# 2-EXS82.net
KiCad netlist of a schematic drawn in Altium Designer
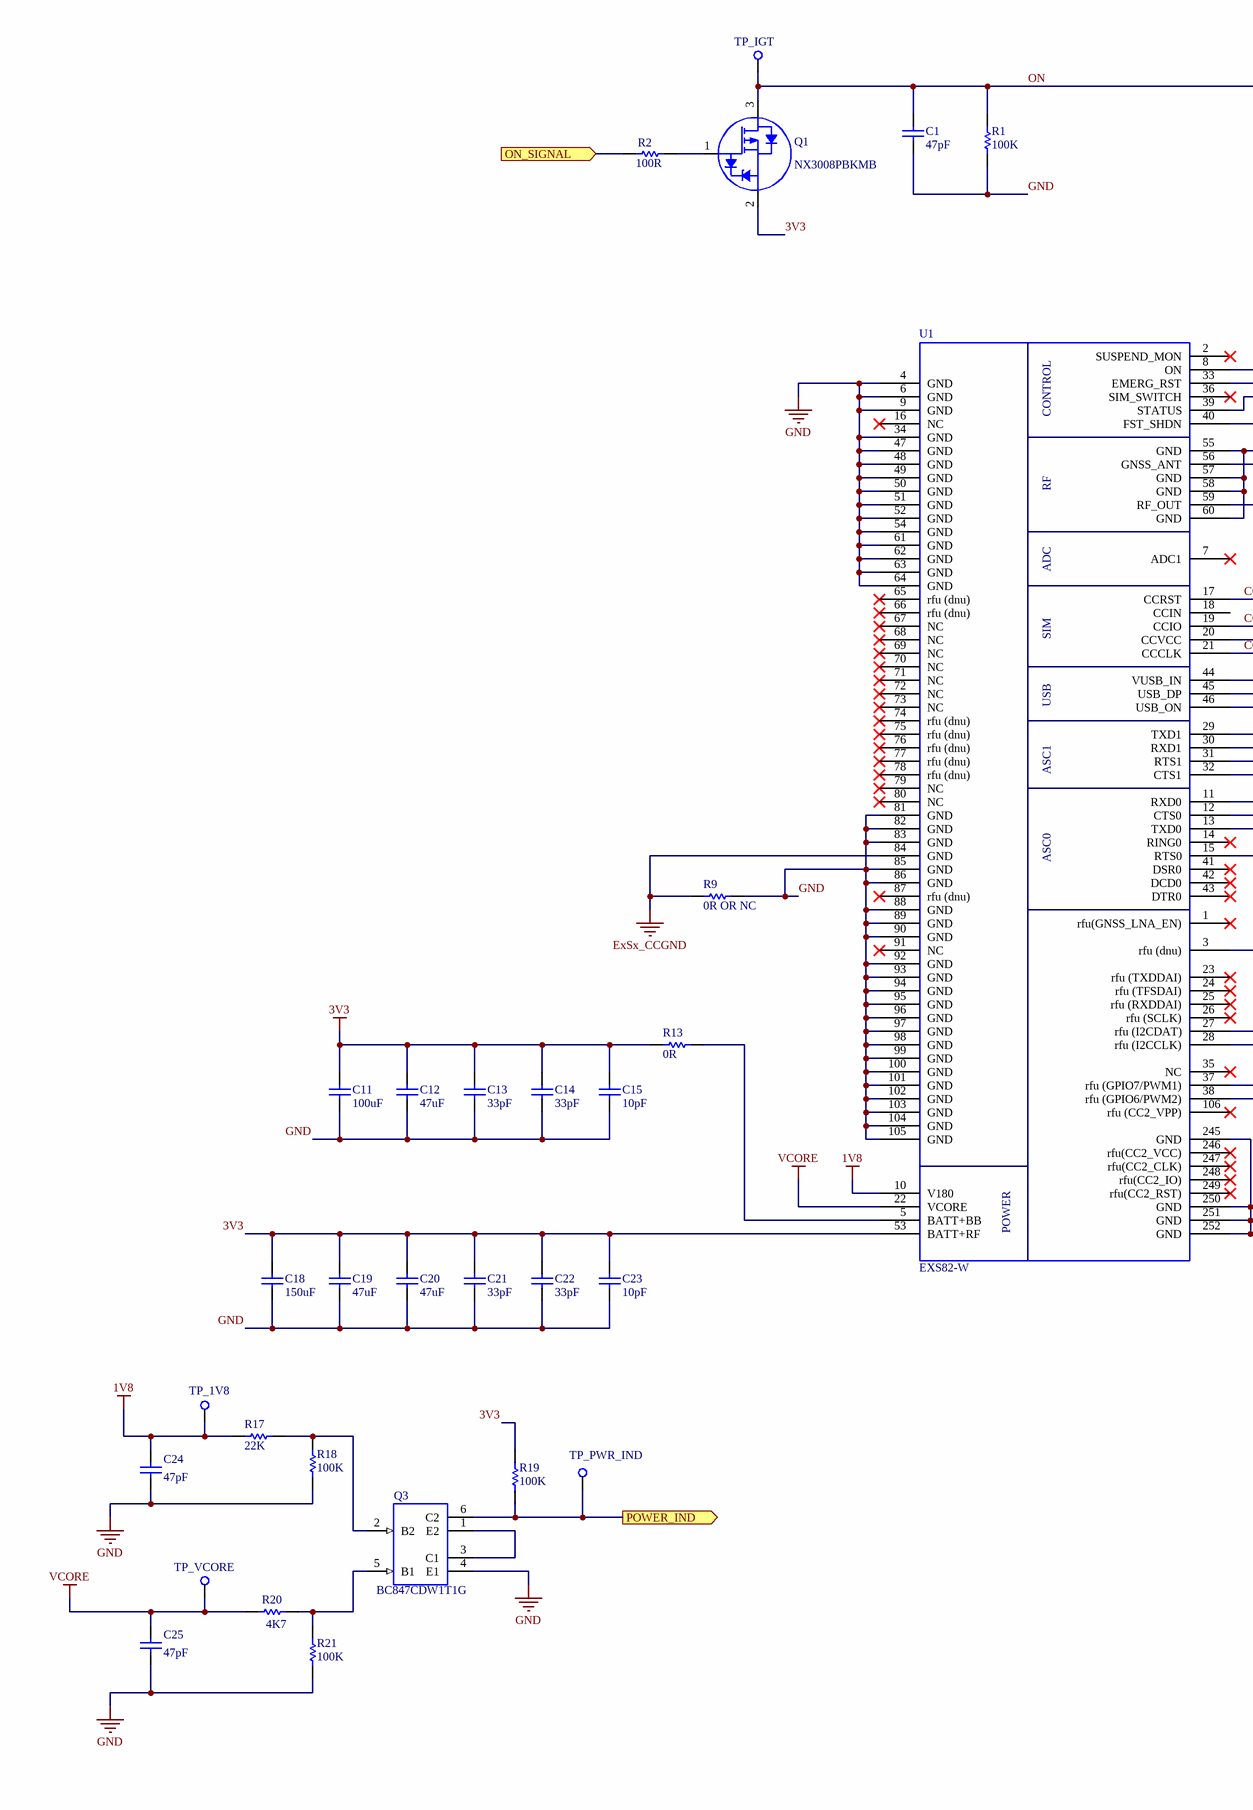
[diagram p0: 2-EXS82.SchDoc, left]
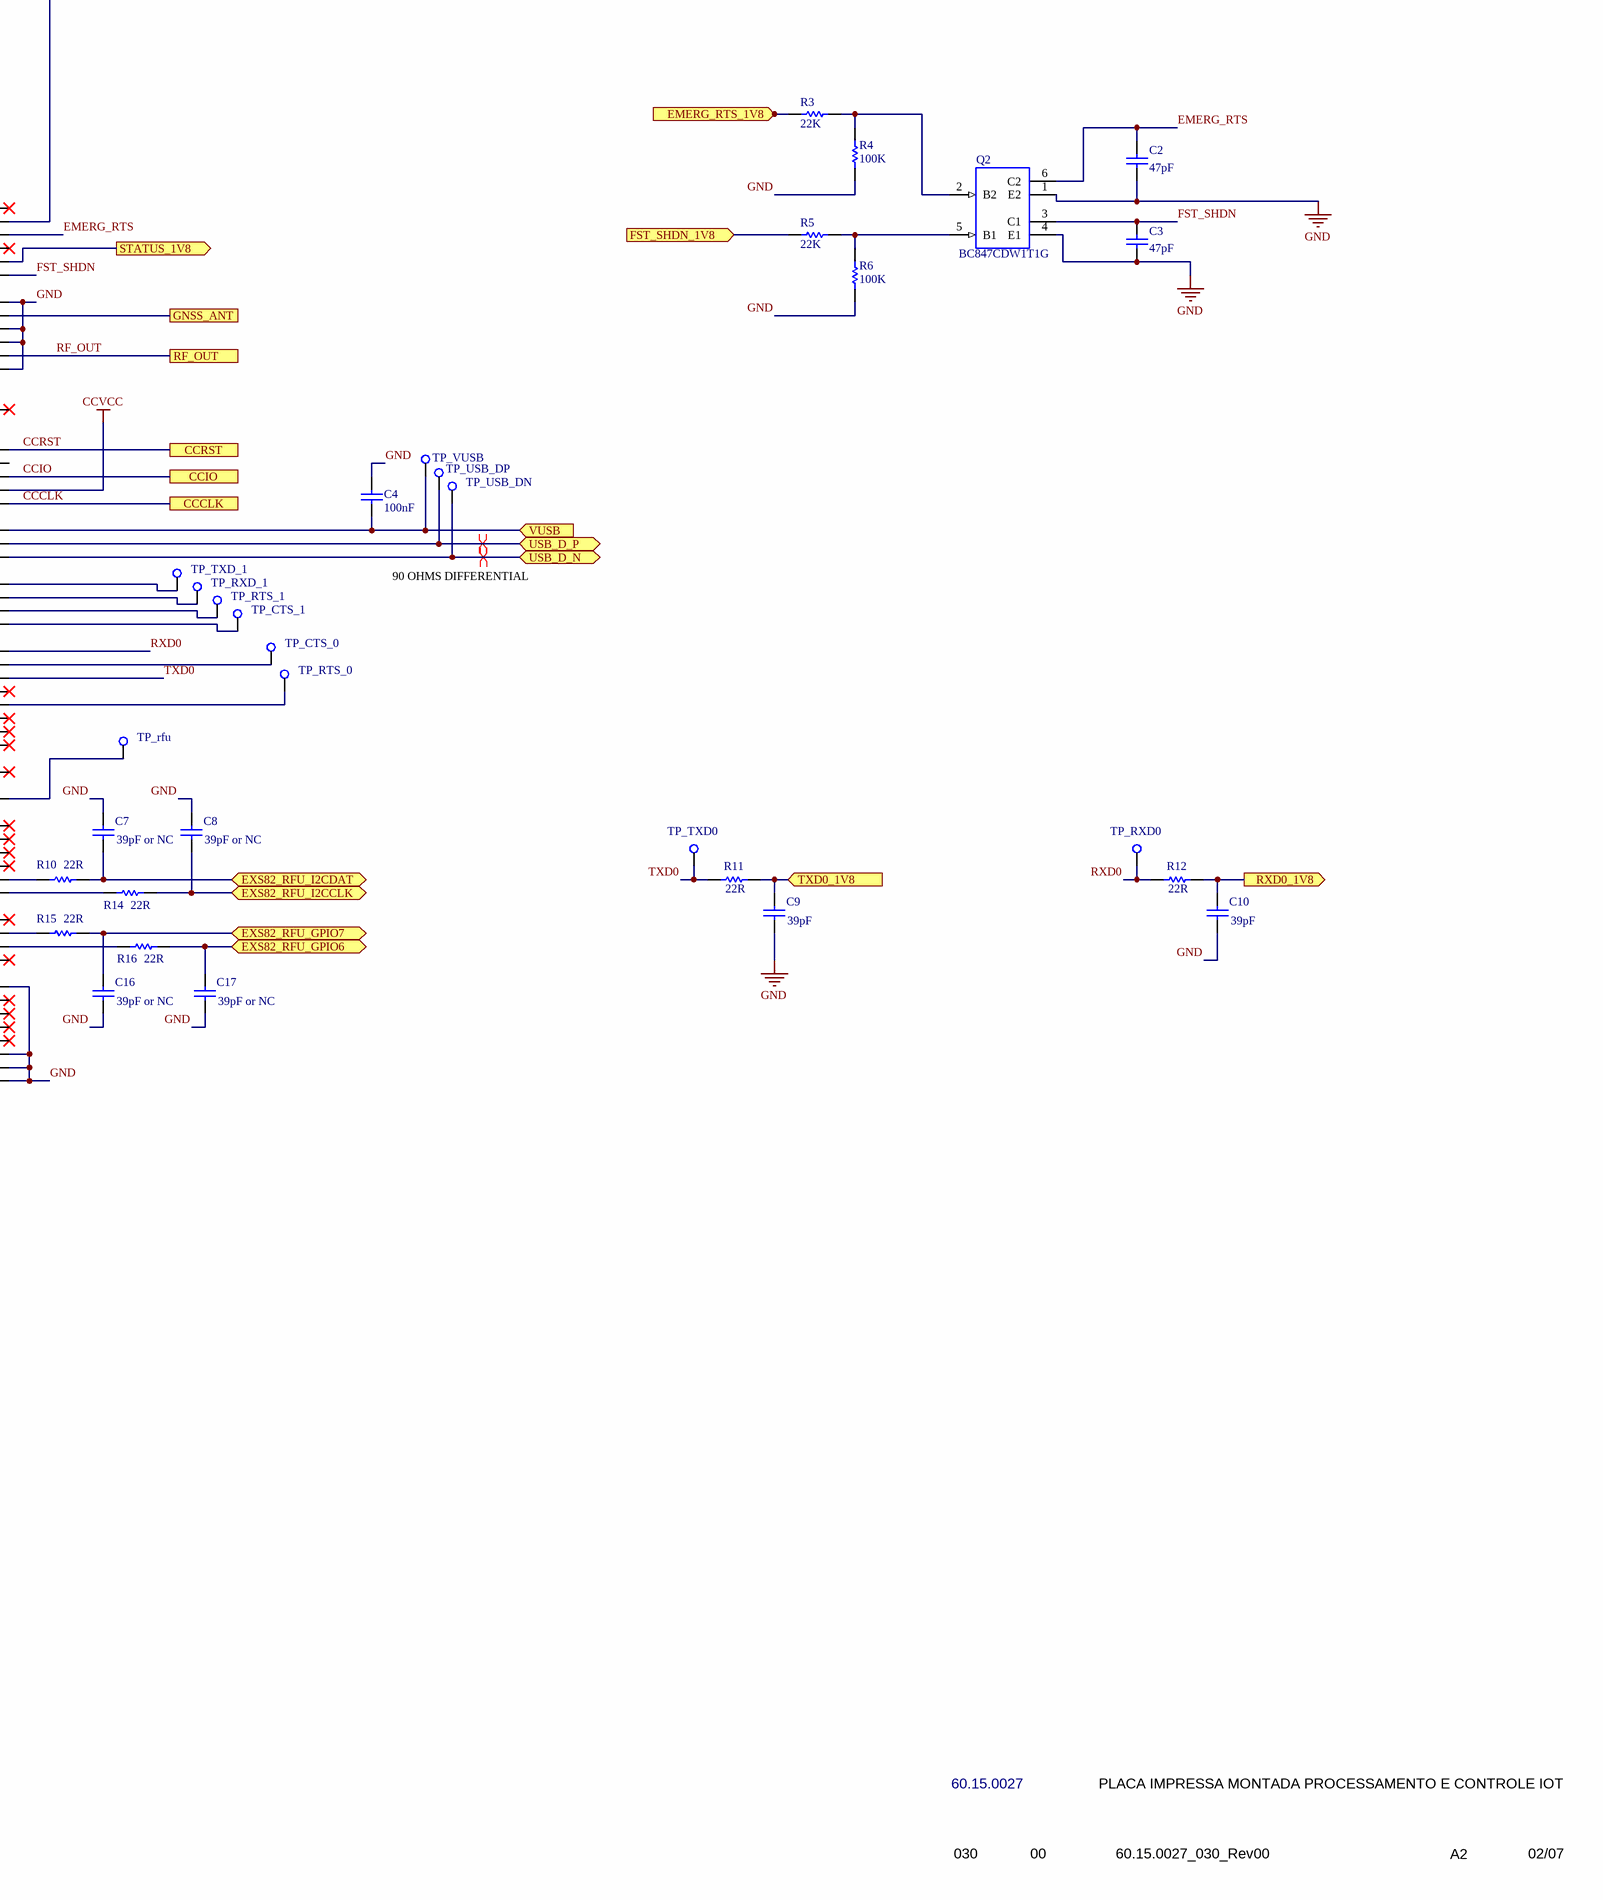
[diagram p1: 2-EXS82.SchDoc, right]

(export (version "E")
  (design (tool "Eeschema 10.0.6"))
  (components
    (comp (ref "C1")
      (value "16.23.0798")
      (footprint "16.23.0798")
      (description "CAPACITOR CERAMICO 47pF 10V 5% C0G SMD 0201")
      (fields (field (name "ALTIUM_UNNAMED_1") "47pF"))
      (libsource (lib "OMNI-CAPACITORES") (part "16.23.0798"))
    )
    (comp (ref "C2")
      (value "16.23.0798")
      (footprint "16.23.0798")
      (description "CAPACITOR CERAMICO 47pF 10V 5% C0G SMD 0201")
      (fields (field (name "ALTIUM_UNNAMED_1") "47pF"))
      (libsource (lib "OMNI-CAPACITORES") (part "16.23.0798"))
    )
    (comp (ref "C3")
      (value "16.23.0798")
      (footprint "16.23.0798")
      (description "CAPACITOR CERAMICO 47pF 10V 5% C0G SMD 0201")
      (fields (field (name "ALTIUM_UNNAMED_1") "47pF"))
      (libsource (lib "OMNI-CAPACITORES") (part "16.23.0798"))
    )
    (comp (ref "C4")
      (value "16.23.0803")
      (footprint "16.23.0803")
      (description "CAPACITOR CERAMICO 100nF 16V 10%% X5R SMD 0201")
      (fields (field (name "ALTIUM_UNNAMED_1") "100nF"))
      (libsource (lib "OMNI-CAPACITORES") (part "16.23.0803"))
    )
    (comp (ref "C7")
      (value "16.23.0802")
      (footprint "16.23.0802")
      (description "CAPACITOR CERAMICO 39pF 100V 5% C0G SMD 0201")
      (fields (field (name "ALTIUM_UNNAMED_1") "39pF or NC"))
      (libsource (lib "OMNI-CAPACITORES") (part "16.23.0802"))
    )
    (comp (ref "C8")
      (value "16.23.0802")
      (footprint "16.23.0802")
      (description "CAPACITOR CERAMICO 39pF 100V 5% C0G SMD 0201")
      (fields (field (name "ALTIUM_UNNAMED_1") "39pF or NC"))
      (libsource (lib "OMNI-CAPACITORES") (part "16.23.0802"))
    )
    (comp (ref "C9")
      (value "16.23.0802")
      (footprint "16.23.0802")
      (description "CAPACITOR CERAMICO 39pF 100V 5% C0G SMD 0201")
      (fields (field (name "ALTIUM_UNNAMED_1") "39pF"))
      (libsource (lib "OMNI-CAPACITORES") (part "16.23.0802"))
    )
    (comp (ref "C10")
      (value "16.23.0802")
      (footprint "16.23.0802")
      (description "CAPACITOR CERAMICO 39pF 100V 5% C0G SMD 0201")
      (fields (field (name "ALTIUM_UNNAMED_1") "39pF"))
      (libsource (lib "OMNI-CAPACITORES") (part "16.23.0802"))
    )
    (comp (ref "C11")
      (value "100uF")
      (footprint "16.23.0804")
      (description "CAPACITOR CERAMICO 100uF 6.3V 10%% X5R SMD 1206")
      (fields (field (name "Comment") "16.23.0804"))
      (libsource (lib "OMNI-CAPACITORES") (part "16.23.0804"))
    )
    (comp (ref "C12")
      (value "16.23.0795")
      (footprint "16.23.0795")
      (description "CERAMICO 47uF 10% 6.3V X5R SMD 1206")
      (fields (field (name "ALTIUM_UNNAMED_1") "47uF"))
      (libsource (lib "OMNI-CAPACITORES") (part "16.23.0795"))
    )
    (comp (ref "C13")
      (value "16.23.0797")
      (footprint "16.23.0797")
      (description "CAPACITOR CERAMICO 33pF 10V 5% C0G SMD 0201")
      (fields (field (name "ALTIUM_UNNAMED_1") "33pF"))
      (libsource (lib "OMNI-CAPACITORES") (part "16.23.0797"))
    )
    (comp (ref "C14")
      (value "16.23.0797")
      (footprint "16.23.0797")
      (description "CAPACITOR CERAMICO 33pF 10V 5% C0G SMD 0201")
      (fields (field (name "ALTIUM_UNNAMED_1") "33pF"))
      (libsource (lib "OMNI-CAPACITORES") (part "16.23.0797"))
    )
    (comp (ref "C15")
      (value "16.23.0799")
      (footprint "16.23.0799")
      (description "CAPACITOR CERAMICO 10pF 25V 5% C0G SMD 0201")
      (fields (field (name "ALTIUM_UNNAMED_1") "10pF"))
      (libsource (lib "OMNI-CAPACITORES") (part "16.23.0799"))
    )
    (comp (ref "C16")
      (value "16.23.0802")
      (footprint "16.23.0802")
      (description "CAPACITOR CERAMICO 39pF 100V 5% C0G SMD 0201")
      (fields (field (name "ALTIUM_UNNAMED_1") "39pF or NC"))
      (libsource (lib "OMNI-CAPACITORES") (part "16.23.0802"))
    )
    (comp (ref "C17")
      (value "16.23.0802")
      (footprint "16.23.0802")
      (description "CAPACITOR CERAMICO 39pF 100V 5% C0G SMD 0201")
      (fields (field (name "ALTIUM_UNNAMED_1") "39pF or NC"))
      (libsource (lib "OMNI-CAPACITORES") (part "16.23.0802"))
    )
    (comp (ref "C18")
      (value "16.23.0789")
      (footprint "16.23.0789")
      (description "CAPACITOR CERAMICO 150uF 20% 6.3V X5R SMD 1206")
      (fields (field (name "ALTIUM_UNNAMED_1") "150uF"))
      (libsource (lib "OMNI-CAPACITORES") (part "16.23.0789"))
    )
    (comp (ref "C19")
      (value "16.23.0795")
      (footprint "16.23.0795")
      (description "CERAMICO 47uF 10% 6.3V X5R SMD 1206")
      (fields (field (name "ALTIUM_UNNAMED_1") "47uF"))
      (libsource (lib "OMNI-CAPACITORES") (part "16.23.0795"))
    )
    (comp (ref "C20")
      (value "16.23.0795")
      (footprint "16.23.0795")
      (description "CERAMICO 47uF 10% 6.3V X5R SMD 1206")
      (fields (field (name "ALTIUM_UNNAMED_1") "47uF"))
      (libsource (lib "OMNI-CAPACITORES") (part "16.23.0795"))
    )
    (comp (ref "C21")
      (value "16.23.0797")
      (footprint "16.23.0797")
      (description "CAPACITOR CERAMICO 33pF 10V 5% C0G SMD 0201")
      (fields (field (name "ALTIUM_UNNAMED_1") "33pF"))
      (libsource (lib "OMNI-CAPACITORES") (part "16.23.0797"))
    )
    (comp (ref "C22")
      (value "16.23.0797")
      (footprint "16.23.0797")
      (description "CAPACITOR CERAMICO 33pF 10V 5% C0G SMD 0201")
      (fields (field (name "ALTIUM_UNNAMED_1") "33pF"))
      (libsource (lib "OMNI-CAPACITORES") (part "16.23.0797"))
    )
    (comp (ref "C23")
      (value "16.23.0799")
      (footprint "16.23.0799")
      (description "CAPACITOR CERAMICO 10pF 25V 5% C0G SMD 0201")
      (fields (field (name "ALTIUM_UNNAMED_1") "10pF"))
      (libsource (lib "OMNI-CAPACITORES") (part "16.23.0799"))
    )
    (comp (ref "C24")
      (value "16.23.0798")
      (footprint "16.23.0798")
      (description "CAPACITOR CERAMICO 47pF 10V 5% C0G SMD 0201")
      (fields (field (name "ALTIUM_UNNAMED_1") "47pF"))
      (libsource (lib "OMNI-CAPACITORES") (part "16.23.0798"))
    )
    (comp (ref "C25")
      (value "16.23.0798")
      (footprint "16.23.0798")
      (description "CAPACITOR CERAMICO 47pF 10V 5% C0G SMD 0201")
      (fields (field (name "ALTIUM_UNNAMED_1") "47pF"))
      (libsource (lib "OMNI-CAPACITORES") (part "16.23.0798"))
    )
    (comp (ref "Q1")
      (value "72.19.0071")
      (footprint "72.19.0071")
      (description "MOSFET CANAL P SMD 30V 230mA SOT883B")
      (fields (field (name "ALTIUM_UNNAMED_1") "NX3008PBKMB"))
      (libsource (lib "OMNI-TRANSISTORES") (part "72.19.0071"))
    )
    (comp (ref "Q2")
      (value "72.26.0005")
      (footprint "72.26.0005")
      (description "TRANSISTOR DUPLO NPN BC847 SMD SOT363")
      (fields (field (name "ALTIUM_UNNAMED_1") "BC847CDW1T1G"))
      (libsource (lib "OMNI-TRANSISTORES") (part "72.26.0005"))
    )
    (comp (ref "Q3")
      (value "72.26.0005")
      (footprint "72.26.0005")
      (description "TRANSISTOR DUPLO NPN BC847 SMD SOT363")
      (fields (field (name "ALTIUM_UNNAMED_1") "BC847CDW1T1G"))
      (libsource (lib "OMNI-TRANSISTORES") (part "72.26.0005"))
    )
    (comp (ref "R1")
      (value "100K")
      (footprint "66.24.1346")
      (description "RESISTOR THICK FILM 50mW 100K OHMS 1% SMD 0201")
      (fields (field (name "Comment") "66.24.1346"))
      (libsource (lib "OMNI-RESISTORES") (part "66.24.1346"))
    )
    (comp (ref "R2")
      (value "100R")
      (footprint "66.24.1342")
      (description "RESISTOR THICK FILM 50mW 100 OHMS 1% SMD 0201")
      (fields (field (name "Comment") "66.24.1342"))
      (libsource (lib "OMNI-RESISTORES") (part "66.24.1342"))
    )
    (comp (ref "R3")
      (value "22K")
      (footprint "66.24.1344")
      (description "RESISTOR THICK FILM 50mW 22K OHMS 1% SMD 0201")
      (fields (field (name "Comment") "66.24.1344"))
      (libsource (lib "OMNI-RESISTORES") (part "66.24.1344"))
    )
    (comp (ref "R4")
      (value "100K")
      (footprint "66.24.1346")
      (description "RESISTOR THICK FILM 50mW 100K OHMS 1% SMD 0201")
      (fields (field (name "Comment") "66.24.1346"))
      (libsource (lib "OMNI-RESISTORES") (part "66.24.1346"))
    )
    (comp (ref "R5")
      (value "22K")
      (footprint "66.24.1344")
      (description "RESISTOR THICK FILM 50mW 22K OHMS 1% SMD 0201")
      (fields (field (name "Comment") "66.24.1344"))
      (libsource (lib "OMNI-RESISTORES") (part "66.24.1344"))
    )
    (comp (ref "R6")
      (value "100K")
      (footprint "66.24.1346")
      (description "RESISTOR THICK FILM 50mW 100K OHMS 1% SMD 0201")
      (fields (field (name "Comment") "66.24.1346"))
      (libsource (lib "OMNI-RESISTORES") (part "66.24.1346"))
    )
    (comp (ref "R9")
      (value "0R OR NC")
      (footprint "66.24.1337")
      (description "RESISTOR THICK FILM 0,1W 0 OHMS SMD 0603")
      (fields (field (name "Comment") "66.24.1337"))
      (libsource (lib "OMNI-RESISTORES") (part "66.24.1337"))
    )
    (comp (ref "R10")
      (value "22R")
      (footprint "66.24.1343")
      (description "RESISTOR THICK FILM 50mW 22 OHMS 1% SMD 0201")
      (fields (field (name "Comment") "66.24.1343"))
      (libsource (lib "OMNI-RESISTORES") (part "66.24.1343"))
    )
    (comp (ref "R11")
      (value "22R")
      (footprint "66.24.1343")
      (description "RESISTOR THICK FILM 50mW 22 OHMS 1% SMD 0201")
      (fields (field (name "Comment") "66.24.1343"))
      (libsource (lib "OMNI-RESISTORES") (part "66.24.1343"))
    )
    (comp (ref "R12")
      (value "22R")
      (footprint "66.24.1343")
      (description "RESISTOR THICK FILM 50mW 22 OHMS 1% SMD 0201")
      (fields (field (name "Comment") "66.24.1343"))
      (libsource (lib "OMNI-RESISTORES") (part "66.24.1343"))
    )
    (comp (ref "R13")
      (value "0R")
      (footprint "66.24.1337")
      (description "RESISTOR THICK FILM 0,1W 0 OHMS SMD 0603")
      (fields (field (name "Comment") "66.24.1337"))
      (libsource (lib "OMNI-RESISTORES") (part "66.24.1337"))
    )
    (comp (ref "R14")
      (value "22R")
      (footprint "66.24.1343")
      (description "RESISTOR THICK FILM 50mW 22 OHMS 1% SMD 0201")
      (fields (field (name "Comment") "66.24.1343"))
      (libsource (lib "OMNI-RESISTORES") (part "66.24.1343"))
    )
    (comp (ref "R15")
      (value "22R")
      (footprint "66.24.1343")
      (description "RESISTOR THICK FILM 50mW 22 OHMS 1% SMD 0201")
      (fields (field (name "Comment") "66.24.1343"))
      (libsource (lib "OMNI-RESISTORES") (part "66.24.1343"))
    )
    (comp (ref "R16")
      (value "22R")
      (footprint "66.24.1343")
      (description "RESISTOR THICK FILM 50mW 22 OHMS 1% SMD 0201")
      (fields (field (name "Comment") "66.24.1343"))
      (libsource (lib "OMNI-RESISTORES") (part "66.24.1343"))
    )
    (comp (ref "R17")
      (value "22K")
      (footprint "66.24.1344")
      (description "RESISTOR THICK FILM 50mW 22K OHMS 1% SMD 0201")
      (fields (field (name "Comment") "66.24.1344"))
      (libsource (lib "OMNI-RESISTORES") (part "66.24.1344"))
    )
    (comp (ref "R18")
      (value "100K")
      (footprint "66.24.1346")
      (description "RESISTOR THICK FILM 50mW 100K OHMS 1% SMD 0201")
      (fields (field (name "Comment") "66.24.1346"))
      (libsource (lib "OMNI-RESISTORES") (part "66.24.1346"))
    )
    (comp (ref "R19")
      (value "100K")
      (footprint "66.24.1346")
      (description "RESISTOR THICK FILM 50mW 100K OHMS 1% SMD 0201")
      (fields (field (name "Comment") "66.24.1346"))
      (libsource (lib "OMNI-RESISTORES") (part "66.24.1346"))
    )
    (comp (ref "R20")
      (value "4K7")
      (footprint "66.24.1345")
      (description "RESISTOR THICK FILM 50mW 4K7 OHMS 1% SMD 0201")
      (fields (field (name "Comment") "66.24.1345"))
      (libsource (lib "OMNI-RESISTORES") (part "66.24.1345"))
    )
    (comp (ref "R21")
      (value "100K")
      (footprint "66.24.1346")
      (description "RESISTOR THICK FILM 50mW 100K OHMS 1% SMD 0201")
      (fields (field (name "Comment") "66.24.1346"))
      (libsource (lib "OMNI-RESISTORES") (part "66.24.1346"))
    )
    (comp (ref "TP_1V8")
      (value "TESTPOINT")
      (footprint "TESTPOINT-60MILS")
      (description "PONTO DE TESTE PARA CAMA DE PREGO")
      (libsource (lib "OMNI-SEM-COD") (part "TESTPOINT-60MILS"))
    )
    (comp (ref "TP_CTS_0")
      (value "TESTPOINT")
      (footprint "TESTPOINT-60MILS")
      (description "PONTO DE TESTE PARA CAMA DE PREGO")
      (libsource (lib "OMNI-SEM-COD") (part "TESTPOINT-60MILS"))
    )
    (comp (ref "TP_CTS_1")
      (value "TESTPOINT")
      (footprint "TESTPOINT-60MILS")
      (description "PONTO DE TESTE PARA CAMA DE PREGO")
      (libsource (lib "OMNI-SEM-COD") (part "TESTPOINT-60MILS"))
    )
    (comp (ref "TP_IGT")
      (value "TESTPOINT")
      (footprint "TESTPOINT-60MILS")
      (description "PONTO DE TESTE PARA CAMA DE PREGO")
      (libsource (lib "OMNI-SEM-COD") (part "TESTPOINT-60MILS"))
    )
    (comp (ref "TP_PWR_IND")
      (value "TESTPOINT")
      (footprint "TESTPOINT-60MILS")
      (description "PONTO DE TESTE PARA CAMA DE PREGO")
      (libsource (lib "OMNI-SEM-COD") (part "TESTPOINT-60MILS"))
    )
    (comp (ref "TP_rfu")
      (value "TESTPOINT")
      (footprint "TESTPOINT-60MILS")
      (description "PONTO DE TESTE PARA CAMA DE PREGO")
      (libsource (lib "OMNI-SEM-COD") (part "TESTPOINT-60MILS"))
    )
    (comp (ref "TP_RTS_0")
      (value "TESTPOINT")
      (footprint "TESTPOINT-60MILS")
      (description "PONTO DE TESTE PARA CAMA DE PREGO")
      (libsource (lib "OMNI-SEM-COD") (part "TESTPOINT-60MILS"))
    )
    (comp (ref "TP_RTS_1")
      (value "TESTPOINT")
      (footprint "TESTPOINT-60MILS")
      (description "PONTO DE TESTE PARA CAMA DE PREGO")
      (libsource (lib "OMNI-SEM-COD") (part "TESTPOINT-60MILS"))
    )
    (comp (ref "TP_RXD0")
      (value "TESTPOINT")
      (footprint "TESTPOINT-60MILS")
      (description "PONTO DE TESTE PARA CAMA DE PREGO")
      (libsource (lib "OMNI-SEM-COD") (part "TESTPOINT-60MILS"))
    )
    (comp (ref "TP_RXD_1")
      (value "TESTPOINT")
      (footprint "TESTPOINT-60MILS")
      (description "PONTO DE TESTE PARA CAMA DE PREGO")
      (libsource (lib "OMNI-SEM-COD") (part "TESTPOINT-60MILS"))
    )
    (comp (ref "TP_TXD0")
      (value "TESTPOINT")
      (footprint "TESTPOINT-60MILS")
      (description "PONTO DE TESTE PARA CAMA DE PREGO")
      (libsource (lib "OMNI-SEM-COD") (part "TESTPOINT-60MILS"))
    )
    (comp (ref "TP_TXD_1")
      (value "TESTPOINT")
      (footprint "TESTPOINT-60MILS")
      (description "PONTO DE TESTE PARA CAMA DE PREGO")
      (libsource (lib "OMNI-SEM-COD") (part "TESTPOINT-60MILS"))
    )
    (comp (ref "TP_USB_DN")
      (value "TESTPOINT")
      (footprint "TESTPOINT-60MILS")
      (description "PONTO DE TESTE PARA CAMA DE PREGO")
      (libsource (lib "OMNI-SEM-COD") (part "TESTPOINT-60MILS"))
    )
    (comp (ref "TP_USB_DP")
      (value "TESTPOINT")
      (footprint "TESTPOINT-60MILS")
      (description "PONTO DE TESTE PARA CAMA DE PREGO")
      (libsource (lib "OMNI-SEM-COD") (part "TESTPOINT-60MILS"))
    )
    (comp (ref "TP_VCORE")
      (value "TESTPOINT")
      (footprint "TESTPOINT-60MILS")
      (description "PONTO DE TESTE PARA CAMA DE PREGO")
      (libsource (lib "OMNI-SEM-COD") (part "TESTPOINT-60MILS"))
    )
    (comp (ref "TP_VUSB")
      (value "TESTPOINT")
      (footprint "TESTPOINT-60MILS")
      (description "PONTO DE TESTE PARA CAMA DE PREGO")
      (libsource (lib "OMNI-SEM-COD") (part "TESTPOINT-60MILS"))
    )
    (comp (ref "U1")
      (value "EXS82-W")
      (footprint "24.12.0081")
      (description "CIRCUITO INTEGRADO DIG MOD COMUNICACAO MULTI REDES EXS82-W")
      (fields (field (name "Comment") "24.12.0081"))
      (libsource (lib "OMNI-CI´S DIGITAIS") (part "24.12.0081"))
    )
  )
  (nets
    (net (code "1") (name "/CCCLK") (class "Default")
      (node (ref "U1") (pin "21") (pinfunction "CCCLK_21") (pintype "passive"))
    )
    (net (code "2") (name "/CCIO") (class "Default")
      (node (ref "U1") (pin "19") (pinfunction "CCIO_19") (pintype "passive"))
    )
    (net (code "3") (name "/CCRST") (class "Default")
      (node (ref "U1") (pin "17") (pinfunction "CCRST_17") (pintype "passive"))
    )
    (net (code "4") (name "/EMERG_RTS") (class "Default")
      (node (ref "C2") (pin "2") (pinfunction "2_2") (pintype "passive"))
      (node (ref "Q2") (pin "6") (pinfunction "C2_6") (pintype "open_collector"))
      (node (ref "U1") (pin "33") (pinfunction "EMERG_RST_33") (pintype "passive"))
    )
    (net (code "5") (name "/EMERG_RTS_1V8") (class "Default")
      (node (ref "R3") (pin "1") (pinfunction "1_1") (pintype "passive"))
    )
    (net (code "6") (name "/EXS82_RFU_GPIO6") (class "Default")
      (node (ref "C17") (pin "2") (pinfunction "2_2") (pintype "passive"))
      (node (ref "R16") (pin "2") (pinfunction "2_2") (pintype "passive"))
    )
    (net (code "7") (name "/EXS82_RFU_GPIO7") (class "Default")
      (node (ref "C16") (pin "2") (pinfunction "2_2") (pintype "passive"))
      (node (ref "R15") (pin "2") (pinfunction "2_2") (pintype "passive"))
    )
    (net (code "8") (name "/EXS82_RFU_I2CCLK") (class "Default")
      (node (ref "C8") (pin "1") (pinfunction "1_1") (pintype "passive"))
      (node (ref "R14") (pin "2") (pinfunction "2_2") (pintype "passive"))
    )
    (net (code "9") (name "/EXS82_RFU_I2CDAT") (class "Default")
      (node (ref "C7") (pin "1") (pinfunction "1_1") (pintype "passive"))
      (node (ref "R10") (pin "2") (pinfunction "2_2") (pintype "passive"))
    )
    (net (code "10") (name "/FST_SHDN") (class "Default")
      (node (ref "C3") (pin "2") (pinfunction "2_2") (pintype "passive"))
      (node (ref "Q2") (pin "3") (pinfunction "C1_3") (pintype "open_collector"))
      (node (ref "U1") (pin "40") (pinfunction "FST_SHDN_40") (pintype "passive"))
    )
    (net (code "11") (name "/FST_SHDN_1V8") (class "Default")
      (node (ref "R5") (pin "1") (pinfunction "1_1") (pintype "passive"))
    )
    (net (code "12") (name "/GNSS_ANT") (class "Default")
      (node (ref "U1") (pin "56") (pinfunction "GNSS_ANT_56") (pintype "passive"))
    )
    (net (code "13") (name "/ON") (class "Default")
      (node (ref "C1") (pin "2") (pinfunction "2_2") (pintype "passive"))
      (node (ref "Q1") (pin "3") (pinfunction "D_3") (pintype "passive"))
      (node (ref "R1") (pin "2") (pinfunction "2_2") (pintype "passive"))
      (node (ref "TP_IGT") (pin "1") (pinfunction "TP_1") (pintype "passive"))
      (node (ref "U1") (pin "8") (pinfunction "ON_8") (pintype "passive"))
    )
    (net (code "14") (name "/ON_SIGNAL") (class "Default")
      (node (ref "R2") (pin "1") (pinfunction "1_1") (pintype "passive"))
    )
    (net (code "15") (name "/POWER_IND") (class "Default")
      (node (ref "Q3") (pin "6") (pinfunction "C2_6") (pintype "open_collector"))
      (node (ref "R19") (pin "1") (pinfunction "1_1") (pintype "passive"))
      (node (ref "TP_PWR_IND") (pin "1") (pinfunction "TP_1") (pintype "passive"))
    )
    (net (code "16") (name "/RF_OUT") (class "Default")
      (node (ref "U1") (pin "59") (pinfunction "RF_OUT_59") (pintype "passive"))
    )
    (net (code "17") (name "/RXD0") (class "Default")
      (node (ref "R12") (pin "1") (pinfunction "1_1") (pintype "passive"))
      (node (ref "TP_RXD0") (pin "1") (pinfunction "TP_1") (pintype "passive"))
      (node (ref "U1") (pin "11") (pinfunction "RXD0_11") (pintype "passive"))
    )
    (net (code "18") (name "/RXD0_1V8") (class "Default")
      (node (ref "C10") (pin "2") (pinfunction "2_2") (pintype "passive"))
      (node (ref "R12") (pin "2") (pinfunction "2_2") (pintype "passive"))
    )
    (net (code "19") (name "/STATUS_1V8") (class "Default")
      (node (ref "U1") (pin "39") (pinfunction "STATUS_39") (pintype "passive"))
    )
    (net (code "20") (name "/TXD0") (class "Default")
      (node (ref "R11") (pin "1") (pinfunction "1_1") (pintype "passive"))
      (node (ref "TP_TXD0") (pin "1") (pinfunction "TP_1") (pintype "passive"))
      (node (ref "U1") (pin "13") (pinfunction "TXD0_13") (pintype "passive"))
    )
    (net (code "21") (name "/TXD0_1V8") (class "Default")
      (node (ref "C9") (pin "2") (pinfunction "2_2") (pintype "passive"))
      (node (ref "R11") (pin "2") (pinfunction "2_2") (pintype "passive"))
    )
    (net (code "22") (name "/USB_D_N") (class "Default")
      (node (ref "TP_USB_DN") (pin "1") (pinfunction "TP_1") (pintype "passive"))
      (node (ref "U1") (pin "46") (pinfunction "USB_ON_46") (pintype "passive"))
    )
    (net (code "23") (name "/USB_D_P") (class "Default")
      (node (ref "TP_USB_DP") (pin "1") (pinfunction "TP_1") (pintype "passive"))
      (node (ref "U1") (pin "45") (pinfunction "USB_DP_45") (pintype "passive"))
    )
    (net (code "24") (name "/VUSB") (class "Default")
      (node (ref "C4") (pin "1") (pinfunction "1_1") (pintype "passive"))
      (node (ref "TP_VUSB") (pin "1") (pinfunction "TP_1") (pintype "passive"))
      (node (ref "U1") (pin "44") (pinfunction "VUSB_IN_44") (pintype "passive"))
    )
    (net (code "25") (name "1V8") (class "Default")
      (node (ref "C24") (pin "2") (pinfunction "2_2") (pintype "passive"))
      (node (ref "R17") (pin "1") (pinfunction "1_1") (pintype "passive"))
      (node (ref "TP_1V8") (pin "1") (pinfunction "TP_1") (pintype "passive"))
      (node (ref "U1") (pin "10") (pinfunction "V180_10") (pintype "passive"))
    )
    (net (code "26") (name "3V3") (class "Default")
      (node (ref "C11") (pin "2") (pinfunction "2_2") (pintype "passive"))
      (node (ref "C12") (pin "1") (pinfunction "1_1") (pintype "passive"))
      (node (ref "C13") (pin "2") (pinfunction "2_2") (pintype "passive"))
      (node (ref "C14") (pin "2") (pinfunction "2_2") (pintype "passive"))
      (node (ref "C15") (pin "2") (pinfunction "2_2") (pintype "passive"))
      (node (ref "C18") (pin "1") (pinfunction "1_1") (pintype "passive"))
      (node (ref "C19") (pin "1") (pinfunction "1_1") (pintype "passive"))
      (node (ref "C20") (pin "1") (pinfunction "1_1") (pintype "passive"))
      (node (ref "C21") (pin "2") (pinfunction "2_2") (pintype "passive"))
      (node (ref "C22") (pin "2") (pinfunction "2_2") (pintype "passive"))
      (node (ref "C23") (pin "2") (pinfunction "2_2") (pintype "passive"))
      (node (ref "Q1") (pin "2") (pinfunction "S_2") (pintype "passive"))
      (node (ref "R13") (pin "1") (pinfunction "1_1") (pintype "passive"))
      (node (ref "R19") (pin "2") (pinfunction "2_2") (pintype "passive"))
      (node (ref "U1") (pin "53") (pinfunction "BATT+RF_53") (pintype "passive"))
    )
    (net (code "27") (name "CCVCC") (class "Default")
      (node (ref "U1") (pin "20") (pinfunction "CCVCC_20") (pintype "passive"))
    )
    (net (code "28") (name "ExSx_CCGND") (class "Default")
      (node (ref "R9") (pin "1") (pinfunction "1_1") (pintype "passive"))
      (node (ref "U1") (pin "84") (pinfunction "GND_84") (pintype "passive"))
    )
    (net (code "29") (name "GND") (class "Default")
      (node (ref "C1") (pin "1") (pinfunction "1_1") (pintype "passive"))
      (node (ref "C10") (pin "1") (pinfunction "1_1") (pintype "passive"))
      (node (ref "C11") (pin "1") (pinfunction "1_1") (pintype "passive"))
      (node (ref "C12") (pin "2") (pinfunction "2_2") (pintype "passive"))
      (node (ref "C13") (pin "1") (pinfunction "1_1") (pintype "passive"))
      (node (ref "C14") (pin "1") (pinfunction "1_1") (pintype "passive"))
      (node (ref "C15") (pin "1") (pinfunction "1_1") (pintype "passive"))
      (node (ref "C16") (pin "1") (pinfunction "1_1") (pintype "passive"))
      (node (ref "C17") (pin "1") (pinfunction "1_1") (pintype "passive"))
      (node (ref "C18") (pin "2") (pinfunction "2_2") (pintype "passive"))
      (node (ref "C19") (pin "2") (pinfunction "2_2") (pintype "passive"))
      (node (ref "C2") (pin "1") (pinfunction "1_1") (pintype "passive"))
      (node (ref "C20") (pin "2") (pinfunction "2_2") (pintype "passive"))
      (node (ref "C21") (pin "1") (pinfunction "1_1") (pintype "passive"))
      (node (ref "C22") (pin "1") (pinfunction "1_1") (pintype "passive"))
      (node (ref "C23") (pin "1") (pinfunction "1_1") (pintype "passive"))
      (node (ref "C24") (pin "1") (pinfunction "1_1") (pintype "passive"))
      (node (ref "C25") (pin "1") (pinfunction "1_1") (pintype "passive"))
      (node (ref "C3") (pin "1") (pinfunction "1_1") (pintype "passive"))
      (node (ref "C4") (pin "2") (pinfunction "2_2") (pintype "passive"))
      (node (ref "C7") (pin "2") (pinfunction "2_2") (pintype "passive"))
      (node (ref "C8") (pin "2") (pinfunction "2_2") (pintype "passive"))
      (node (ref "C9") (pin "1") (pinfunction "1_1") (pintype "passive"))
      (node (ref "Q2") (pin "1") (pinfunction "E2_1") (pintype "open_emitter"))
      (node (ref "Q2") (pin "4") (pinfunction "E1_4") (pintype "open_emitter"))
      (node (ref "Q3") (pin "4") (pinfunction "E1_4") (pintype "open_emitter"))
      (node (ref "R1") (pin "1") (pinfunction "1_1") (pintype "passive"))
      (node (ref "R18") (pin "1") (pinfunction "1_1") (pintype "passive"))
      (node (ref "R21") (pin "1") (pinfunction "1_1") (pintype "passive"))
      (node (ref "R4") (pin "1") (pinfunction "1_1") (pintype "passive"))
      (node (ref "R6") (pin "1") (pinfunction "1_1") (pintype "passive"))
      (node (ref "R9") (pin "2") (pinfunction "2_2") (pintype "passive"))
      (node (ref "U1") (pin "100") (pinfunction "GND_100") (pintype "passive"))
      (node (ref "U1") (pin "101") (pinfunction "GND_101") (pintype "passive"))
      (node (ref "U1") (pin "102") (pinfunction "GND_102") (pintype "passive"))
      (node (ref "U1") (pin "103") (pinfunction "GND_103") (pintype "passive"))
      (node (ref "U1") (pin "104") (pinfunction "GND_104") (pintype "passive"))
      (node (ref "U1") (pin "105") (pinfunction "GND_105") (pintype "passive"))
      (node (ref "U1") (pin "245") (pinfunction "GND_245") (pintype "passive"))
      (node (ref "U1") (pin "250") (pinfunction "GND_250") (pintype "passive"))
      (node (ref "U1") (pin "251") (pinfunction "GND_251") (pintype "passive"))
      (node (ref "U1") (pin "252") (pinfunction "GND_252") (pintype "passive"))
      (node (ref "U1") (pin "34") (pinfunction "GND_34") (pintype "passive"))
      (node (ref "U1") (pin "4") (pinfunction "GND_4") (pintype "passive"))
      (node (ref "U1") (pin "47") (pinfunction "GND_47") (pintype "passive"))
      (node (ref "U1") (pin "48") (pinfunction "GND_48") (pintype "passive"))
      (node (ref "U1") (pin "49") (pinfunction "GND_49") (pintype "passive"))
      (node (ref "U1") (pin "50") (pinfunction "GND_50") (pintype "passive"))
      (node (ref "U1") (pin "51") (pinfunction "GND_51") (pintype "passive"))
      (node (ref "U1") (pin "52") (pinfunction "GND_52") (pintype "passive"))
      (node (ref "U1") (pin "54") (pinfunction "GND_54") (pintype "passive"))
      (node (ref "U1") (pin "55") (pinfunction "GND_55") (pintype "passive"))
      (node (ref "U1") (pin "57") (pinfunction "GND_57") (pintype "passive"))
      (node (ref "U1") (pin "58") (pinfunction "GND_58") (pintype "passive"))
      (node (ref "U1") (pin "6") (pinfunction "GND_6") (pintype "passive"))
      (node (ref "U1") (pin "60") (pinfunction "GND_60") (pintype "passive"))
      (node (ref "U1") (pin "61") (pinfunction "GND_61") (pintype "passive"))
      (node (ref "U1") (pin "62") (pinfunction "GND_62") (pintype "passive"))
      (node (ref "U1") (pin "63") (pinfunction "GND_63") (pintype "passive"))
      (node (ref "U1") (pin "64") (pinfunction "GND_64") (pintype "passive"))
      (node (ref "U1") (pin "81") (pinfunction "GND_81") (pintype "passive"))
      (node (ref "U1") (pin "82") (pinfunction "GND_82") (pintype "passive"))
      (node (ref "U1") (pin "83") (pinfunction "GND_83") (pintype "passive"))
      (node (ref "U1") (pin "85") (pinfunction "GND_85") (pintype "passive"))
      (node (ref "U1") (pin "86") (pinfunction "GND_86") (pintype "passive"))
      (node (ref "U1") (pin "88") (pinfunction "GND_88") (pintype "passive"))
      (node (ref "U1") (pin "89") (pinfunction "GND_89") (pintype "passive"))
      (node (ref "U1") (pin "9") (pinfunction "GND_9") (pintype "passive"))
      (node (ref "U1") (pin "90") (pinfunction "GND_90") (pintype "passive"))
      (node (ref "U1") (pin "92") (pinfunction "GND_92") (pintype "passive"))
      (node (ref "U1") (pin "93") (pinfunction "GND_93") (pintype "passive"))
      (node (ref "U1") (pin "94") (pinfunction "GND_94") (pintype "passive"))
      (node (ref "U1") (pin "95") (pinfunction "GND_95") (pintype "passive"))
      (node (ref "U1") (pin "96") (pinfunction "GND_96") (pintype "passive"))
      (node (ref "U1") (pin "97") (pinfunction "GND_97") (pintype "passive"))
      (node (ref "U1") (pin "98") (pinfunction "GND_98") (pintype "passive"))
      (node (ref "U1") (pin "99") (pinfunction "GND_99") (pintype "passive"))
    )
    (net (code "30") (name "Net-(Q1-G)") (class "Default")
      (node (ref "Q1") (pin "1") (pinfunction "G_1") (pintype "passive"))
      (node (ref "R2") (pin "2") (pinfunction "2_2") (pintype "passive"))
    )
    (net (code "31") (name "Net-(Q2-B1)") (class "Default")
      (node (ref "Q2") (pin "5") (pinfunction "B1_5") (pintype "input"))
      (node (ref "R5") (pin "2") (pinfunction "2_2") (pintype "passive"))
      (node (ref "R6") (pin "2") (pinfunction "2_2") (pintype "passive"))
    )
    (net (code "32") (name "Net-(Q2-B2)") (class "Default")
      (node (ref "Q2") (pin "2") (pinfunction "B2_2") (pintype "input"))
      (node (ref "R3") (pin "2") (pinfunction "2_2") (pintype "passive"))
      (node (ref "R4") (pin "2") (pinfunction "2_2") (pintype "passive"))
    )
    (net (code "33") (name "Net-(Q3-B1)") (class "Default")
      (node (ref "Q3") (pin "5") (pinfunction "B1_5") (pintype "input"))
      (node (ref "R20") (pin "2") (pinfunction "2_2") (pintype "passive"))
      (node (ref "R21") (pin "2") (pinfunction "2_2") (pintype "passive"))
    )
    (net (code "34") (name "Net-(Q3-B2)") (class "Default")
      (node (ref "Q3") (pin "2") (pinfunction "B2_2") (pintype "input"))
      (node (ref "R17") (pin "2") (pinfunction "2_2") (pintype "passive"))
      (node (ref "R18") (pin "2") (pinfunction "2_2") (pintype "passive"))
    )
    (net (code "35") (name "Net-(Q3-C1)") (class "Default")
      (node (ref "Q3") (pin "1") (pinfunction "E2_1") (pintype "open_emitter"))
      (node (ref "Q3") (pin "3") (pinfunction "C1_3") (pintype "open_collector"))
    )
    (net (code "36") (name "Net-(TP_CTS_0-TP)") (class "Default")
      (node (ref "TP_CTS_0") (pin "1") (pinfunction "TP_1") (pintype "passive"))
      (node (ref "U1") (pin "12") (pinfunction "CTS0_12") (pintype "passive"))
    )
    (net (code "37") (name "Net-(TP_CTS_1-TP)") (class "Default")
      (node (ref "TP_CTS_1") (pin "1") (pinfunction "TP_1") (pintype "passive"))
      (node (ref "U1") (pin "32") (pinfunction "CTS1_32") (pintype "passive"))
    )
    (net (code "38") (name "Net-(TP_RTS_0-TP)") (class "Default")
      (node (ref "TP_RTS_0") (pin "1") (pinfunction "TP_1") (pintype "passive"))
      (node (ref "U1") (pin "15") (pinfunction "RTS0_15") (pintype "passive"))
    )
    (net (code "39") (name "Net-(TP_RTS_1-TP)") (class "Default")
      (node (ref "TP_RTS_1") (pin "1") (pinfunction "TP_1") (pintype "passive"))
      (node (ref "U1") (pin "31") (pinfunction "RTS1_31") (pintype "passive"))
    )
    (net (code "40") (name "Net-(TP_RXD_1-TP)") (class "Default")
      (node (ref "TP_RXD_1") (pin "1") (pinfunction "TP_1") (pintype "passive"))
      (node (ref "U1") (pin "30") (pinfunction "RXD1_30") (pintype "passive"))
    )
    (net (code "41") (name "Net-(TP_TXD_1-TP)") (class "Default")
      (node (ref "TP_TXD_1") (pin "1") (pinfunction "TP_1") (pintype "passive"))
      (node (ref "U1") (pin "29") (pinfunction "TXD1_29") (pintype "passive"))
    )
    (net (code "42") (name "Net-(TP_rfu-TP)") (class "Default")
      (node (ref "TP_rfu") (pin "1") (pinfunction "TP_1") (pintype "passive"))
      (node (ref "U1") (pin "3") (pinfunction "rfu_(dnu)_3") (pintype "passive"))
    )
    (net (code "43") (name "Net-(U1-BATT+BB)") (class "Default")
      (node (ref "R13") (pin "2") (pinfunction "2_2") (pintype "passive"))
      (node (ref "U1") (pin "5") (pinfunction "BATT+BB_5") (pintype "passive"))
    )
    (net (code "44") (name "Net-(U1-rfu_(GPIO6{slash}PWM2))") (class "Default")
      (node (ref "R16") (pin "1") (pinfunction "1_1") (pintype "passive"))
      (node (ref "U1") (pin "38") (pinfunction "rfu_(GPIO6/PWM2)_38") (pintype "passive"))
    )
    (net (code "45") (name "Net-(U1-rfu_(GPIO7{slash}PWM1))") (class "Default")
      (node (ref "R15") (pin "1") (pinfunction "1_1") (pintype "passive"))
      (node (ref "U1") (pin "37") (pinfunction "rfu_(GPIO7/PWM1)_37") (pintype "passive"))
    )
    (net (code "46") (name "Net-(U1-rfu_(I2CCLK))") (class "Default")
      (node (ref "R14") (pin "1") (pinfunction "1_1") (pintype "passive"))
      (node (ref "U1") (pin "28") (pinfunction "rfu_(I2CCLK)_28") (pintype "passive"))
    )
    (net (code "47") (name "Net-(U1-rfu_(I2CDAT))") (class "Default")
      (node (ref "R10") (pin "1") (pinfunction "1_1") (pintype "passive"))
      (node (ref "U1") (pin "27") (pinfunction "rfu_(I2CDAT)_27") (pintype "passive"))
    )
    (net (code "48") (name "VCORE") (class "Default")
      (node (ref "C25") (pin "2") (pinfunction "2_2") (pintype "passive"))
      (node (ref "R20") (pin "1") (pinfunction "1_1") (pintype "passive"))
      (node (ref "TP_VCORE") (pin "1") (pinfunction "TP_1") (pintype "passive"))
      (node (ref "U1") (pin "22") (pinfunction "VCORE_22") (pintype "passive"))
    )
    (net (code "49") (name "unconnected-(U1-ADC1-Pad7)") (class "Default")
      (node (ref "U1") (pin "7") (pinfunction "ADC1_7") (pintype "passive+no_connect"))
    )
    (net (code "50") (name "unconnected-(U1-CCIN-Pad18)") (class "Default")
      (node (ref "U1") (pin "18") (pinfunction "CCIN_18") (pintype "passive"))
    )
    (net (code "51") (name "unconnected-(U1-DCD0-Pad42)") (class "Default")
      (node (ref "U1") (pin "42") (pinfunction "DCD0_42") (pintype "passive+no_connect"))
    )
    (net (code "52") (name "unconnected-(U1-DSR0-Pad41)") (class "Default")
      (node (ref "U1") (pin "41") (pinfunction "DSR0_41") (pintype "passive+no_connect"))
    )
    (net (code "53") (name "unconnected-(U1-DTR0-Pad43)") (class "Default")
      (node (ref "U1") (pin "43") (pinfunction "DTR0_43") (pintype "passive+no_connect"))
    )
    (net (code "54") (name "unconnected-(U1-NC-Pad16)") (class "Default")
      (node (ref "U1") (pin "16") (pinfunction "NC_16") (pintype "passive+no_connect"))
    )
    (net (code "55") (name "unconnected-(U1-NC-Pad35)") (class "Default")
      (node (ref "U1") (pin "35") (pinfunction "NC_35") (pintype "passive+no_connect"))
    )
    (net (code "56") (name "unconnected-(U1-NC-Pad67)") (class "Default")
      (node (ref "U1") (pin "67") (pinfunction "NC_67") (pintype "passive+no_connect"))
    )
    (net (code "57") (name "unconnected-(U1-NC-Pad68)") (class "Default")
      (node (ref "U1") (pin "68") (pinfunction "NC_68") (pintype "passive+no_connect"))
    )
    (net (code "58") (name "unconnected-(U1-NC-Pad69)") (class "Default")
      (node (ref "U1") (pin "69") (pinfunction "NC_69") (pintype "passive+no_connect"))
    )
    (net (code "59") (name "unconnected-(U1-NC-Pad70)") (class "Default")
      (node (ref "U1") (pin "70") (pinfunction "NC_70") (pintype "passive+no_connect"))
    )
    (net (code "60") (name "unconnected-(U1-NC-Pad71)") (class "Default")
      (node (ref "U1") (pin "71") (pinfunction "NC_71") (pintype "passive+no_connect"))
    )
    (net (code "61") (name "unconnected-(U1-NC-Pad72)") (class "Default")
      (node (ref "U1") (pin "72") (pinfunction "NC_72") (pintype "passive+no_connect"))
    )
    (net (code "62") (name "unconnected-(U1-NC-Pad73)") (class "Default")
      (node (ref "U1") (pin "73") (pinfunction "NC_73") (pintype "passive+no_connect"))
    )
    (net (code "63") (name "unconnected-(U1-NC-Pad79)") (class "Default")
      (node (ref "U1") (pin "79") (pinfunction "NC_79") (pintype "passive+no_connect"))
    )
    (net (code "64") (name "unconnected-(U1-NC-Pad80)") (class "Default")
      (node (ref "U1") (pin "80") (pinfunction "NC_80") (pintype "passive+no_connect"))
    )
    (net (code "65") (name "unconnected-(U1-NC-Pad91)") (class "Default")
      (node (ref "U1") (pin "91") (pinfunction "NC_91") (pintype "passive+no_connect"))
    )
    (net (code "66") (name "unconnected-(U1-RING0-Pad14)") (class "Default")
      (node (ref "U1") (pin "14") (pinfunction "RING0_14") (pintype "passive+no_connect"))
    )
    (net (code "67") (name "unconnected-(U1-SIM_SWITCH-Pad36)") (class "Default")
      (node (ref "U1") (pin "36") (pinfunction "SIM_SWITCH_36") (pintype "passive+no_connect"))
    )
    (net (code "68") (name "unconnected-(U1-SUSPEND_MON-Pad2)") (class "Default")
      (node (ref "U1") (pin "2") (pinfunction "SUSPEND_MON_2") (pintype "passive+no_connect"))
    )
    (net (code "69") (name "unconnected-(U1-rfu(CC2_CLK)-Pad247)") (class "Default")
      (node (ref "U1") (pin "247") (pinfunction "rfu(CC2_CLK)_247") (pintype "passive+no_connect"))
    )
    (net (code "70") (name "unconnected-(U1-rfu(CC2_IO)-Pad248)") (class "Default")
      (node (ref "U1") (pin "248") (pinfunction "rfu(CC2_IO)_248") (pintype "passive+no_connect"))
    )
    (net (code "71") (name "unconnected-(U1-rfu(CC2_RST)-Pad249)") (class "Default")
      (node (ref "U1") (pin "249") (pinfunction "rfu(CC2_RST)_249") (pintype "passive+no_connect"))
    )
    (net (code "72") (name "unconnected-(U1-rfu(CC2_VCC)-Pad246)") (class "Default")
      (node (ref "U1") (pin "246") (pinfunction "rfu(CC2_VCC)_246") (pintype "passive+no_connect"))
    )
    (net (code "73") (name "unconnected-(U1-rfu(GNSS_LNA_EN)-Pad1)") (class "Default")
      (node (ref "U1") (pin "1") (pinfunction "rfu(GNSS_LNA_EN)_1") (pintype "passive+no_connect"))
    )
    (net (code "74") (name "unconnected-(U1-rfu_(CC2_VPP)-Pad106)") (class "Default")
      (node (ref "U1") (pin "106") (pinfunction "rfu_(CC2_VPP)_106") (pintype "passive+no_connect"))
    )
    (net (code "75") (name "unconnected-(U1-rfu_(RXDDAI)-Pad25)") (class "Default")
      (node (ref "U1") (pin "25") (pinfunction "rfu_(RXDDAI)_25") (pintype "passive+no_connect"))
    )
    (net (code "76") (name "unconnected-(U1-rfu_(SCLK)-Pad26)") (class "Default")
      (node (ref "U1") (pin "26") (pinfunction "rfu_(SCLK)_26") (pintype "passive+no_connect"))
    )
    (net (code "77") (name "unconnected-(U1-rfu_(TFSDAI)-Pad24)") (class "Default")
      (node (ref "U1") (pin "24") (pinfunction "rfu_(TFSDAI)_24") (pintype "passive+no_connect"))
    )
    (net (code "78") (name "unconnected-(U1-rfu_(TXDDAI)-Pad23)") (class "Default")
      (node (ref "U1") (pin "23") (pinfunction "rfu_(TXDDAI)_23") (pintype "passive+no_connect"))
    )
    (net (code "79") (name "unconnected-(U1-rfu_(dnu)-Pad65)") (class "Default")
      (node (ref "U1") (pin "65") (pinfunction "rfu_(dnu)_65") (pintype "passive+no_connect"))
    )
    (net (code "80") (name "unconnected-(U1-rfu_(dnu)-Pad66)") (class "Default")
      (node (ref "U1") (pin "66") (pinfunction "rfu_(dnu)_66") (pintype "passive+no_connect"))
    )
    (net (code "81") (name "unconnected-(U1-rfu_(dnu)-Pad74)") (class "Default")
      (node (ref "U1") (pin "74") (pinfunction "rfu_(dnu)_74") (pintype "passive+no_connect"))
    )
    (net (code "82") (name "unconnected-(U1-rfu_(dnu)-Pad75)") (class "Default")
      (node (ref "U1") (pin "75") (pinfunction "rfu_(dnu)_75") (pintype "passive+no_connect"))
    )
    (net (code "83") (name "unconnected-(U1-rfu_(dnu)-Pad76)") (class "Default")
      (node (ref "U1") (pin "76") (pinfunction "rfu_(dnu)_76") (pintype "passive+no_connect"))
    )
    (net (code "84") (name "unconnected-(U1-rfu_(dnu)-Pad77)") (class "Default")
      (node (ref "U1") (pin "77") (pinfunction "rfu_(dnu)_77") (pintype "passive+no_connect"))
    )
    (net (code "85") (name "unconnected-(U1-rfu_(dnu)-Pad78)") (class "Default")
      (node (ref "U1") (pin "78") (pinfunction "rfu_(dnu)_78") (pintype "passive+no_connect"))
    )
    (net (code "86") (name "unconnected-(U1-rfu_(dnu)-Pad87)") (class "Default")
      (node (ref "U1") (pin "87") (pinfunction "rfu_(dnu)_87") (pintype "passive+no_connect"))
    )
  )
)
